# abpf.net
KiCad netlist of a schematic drawn in EAGLE
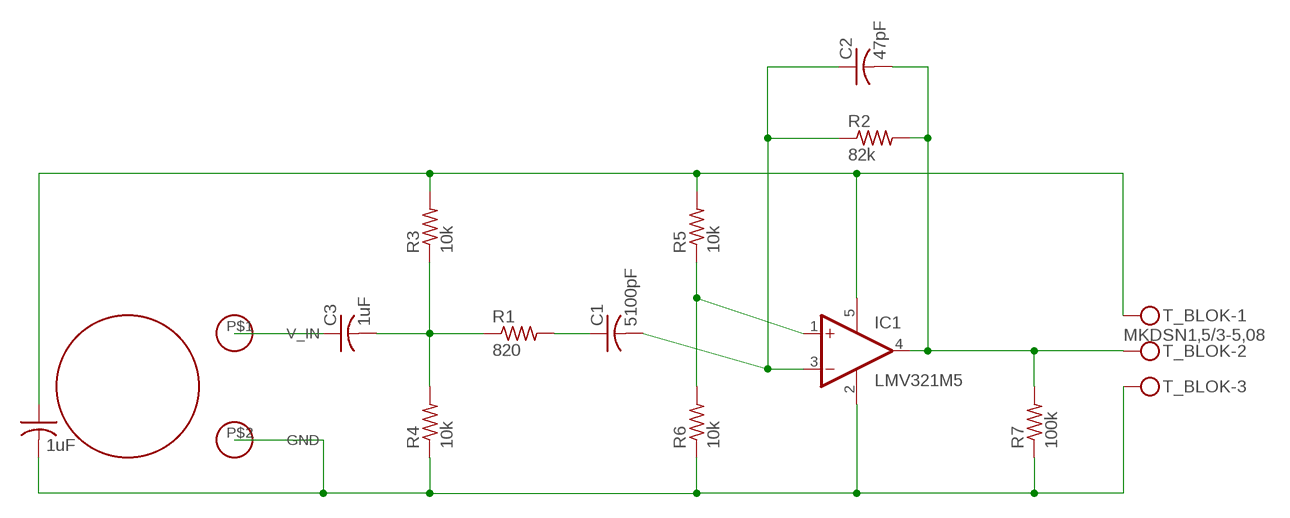
[diagram p0: schematic, sheet 1]

(export (version "E")
  (design (tool "Eeschema 10.0.6"))
  (components
    (comp (ref "C1")
      (value "5100pF")
      (footprint "eagle-import:C0805")
      (libsource (lib "eagle-import") (part "C-USC0805"))
    )
    (comp (ref "C2")
      (value "47pF")
      (footprint "eagle-import:C0805")
      (libsource (lib "eagle-import") (part "C-USC0805"))
    )
    (comp (ref "C3")
      (value "1uF")
      (footprint "eagle-import:C0805")
      (libsource (lib "eagle-import") (part "C-USC0805"))
    )
    (comp (ref "C4")
      (value "1uF")
      (footprint "eagle-import:C0805")
      (libsource (lib "eagle-import") (part "C-USC0805"))
    )
    (comp (ref "IC1")
      (value "LMV321M5")
      (footprint "eagle-import:SOT23-5")
      (libsource (lib "eagle-import") (part "LMV321?M5"))
    )
    (comp (ref "R1")
      (value "820")
      (footprint "eagle-import:R0805")
      (libsource (lib "eagle-import") (part "R-US_R0805"))
    )
    (comp (ref "R2")
      (value "82k")
      (footprint "eagle-import:R0805")
      (libsource (lib "eagle-import") (part "R-US_R0805"))
    )
    (comp (ref "R3")
      (value "10k")
      (footprint "eagle-import:R0805")
      (libsource (lib "eagle-import") (part "R-US_R0805"))
    )
    (comp (ref "R4")
      (value "10k")
      (footprint "eagle-import:R0805")
      (libsource (lib "eagle-import") (part "R-US_R0805"))
    )
    (comp (ref "R5")
      (value "10k")
      (footprint "eagle-import:R0805")
      (libsource (lib "eagle-import") (part "R-US_R0805"))
    )
    (comp (ref "R6")
      (value "10k")
      (footprint "eagle-import:R0805")
      (libsource (lib "eagle-import") (part "R-US_R0805"))
    )
    (comp (ref "R7")
      (value "100k")
      (footprint "eagle-import:R0805")
      (libsource (lib "eagle-import") (part "R-US_R0805"))
    )
    (comp (ref "T_BLOK")
      (value "MKDSN1,5/3-5,08")
      (footprint "eagle-import:MKDSN1,5_3-5,08")
      (libsource (lib "eagle-import") (part "MKDSN1,5/3-5,08"))
    )
    (comp (ref "U$1")
      (value "10MM_USONIC")
      (footprint "eagle-import:10MM_USONIC")
      (libsource (lib "eagle-import") (part "10MM_USONIC"))
    )
  )
  (nets
    (net (code "1") (name "Net-(C1-Pad1)") (class "Default")
      (node (ref "C1") (pin "1") (pinfunction "1_1") (pintype "passive"))
      (node (ref "R1") (pin "2") (pinfunction "2_2") (pintype "passive"))
    )
    (net (code "2") (name "Net-(C3-Pad2)") (class "Default")
      (node (ref "C3") (pin "2") (pinfunction "2_2") (pintype "passive"))
      (node (ref "R1") (pin "1") (pinfunction "1_1") (pintype "passive"))
      (node (ref "R3") (pin "1") (pinfunction "1_1") (pintype "passive"))
      (node (ref "R4") (pin "2") (pinfunction "2_2") (pintype "passive"))
    )
    (net (code "3") (name "Net-(IC1-+IN)") (class "Default")
      (node (ref "IC1") (pin "1") (pinfunction "+IN_1") (pintype "input"))
      (node (ref "R5") (pin "1") (pinfunction "1_1") (pintype "passive"))
      (node (ref "R6") (pin "2") (pinfunction "2_2") (pintype "passive"))
    )
    (net (code "4") (name "Net-(IC1--IN)") (class "Default")
      (node (ref "C1") (pin "2") (pinfunction "2_2") (pintype "passive"))
      (node (ref "C2") (pin "1") (pinfunction "1_1") (pintype "passive"))
      (node (ref "IC1") (pin "3") (pinfunction "-IN_3") (pintype "input"))
      (node (ref "R2") (pin "1") (pinfunction "1_1") (pintype "passive"))
    )
    (net (code "5") (name "Net-(IC1-OUT)") (class "Default")
      (node (ref "C2") (pin "2") (pinfunction "2_2") (pintype "passive"))
      (node (ref "IC1") (pin "4") (pinfunction "OUT_4") (pintype "output"))
      (node (ref "R2") (pin "2") (pinfunction "2_2") (pintype "passive"))
      (node (ref "R7") (pin "2") (pinfunction "2_2") (pintype "passive"))
      (node (ref "T_BLOK") (pin "2") (pinfunction "KL_2") (pintype "passive"))
    )
    (net (code "6") (name "Net-(IC1-V+)") (class "Default")
      (node (ref "C4") (pin "1") (pinfunction "1_1") (pintype "passive"))
      (node (ref "IC1") (pin "5") (pinfunction "V+_5") (pintype "power_in"))
      (node (ref "R3") (pin "2") (pinfunction "2_2") (pintype "passive"))
      (node (ref "R5") (pin "2") (pinfunction "2_2") (pintype "passive"))
      (node (ref "T_BLOK") (pin "1") (pinfunction "KL_1") (pintype "passive"))
    )
    (net (code "7") (name "Net-(IC1-V-)") (class "Default")
      (node (ref "C4") (pin "2") (pinfunction "2_2") (pintype "passive"))
      (node (ref "IC1") (pin "2") (pinfunction "V-_2") (pintype "power_in"))
      (node (ref "R4") (pin "1") (pinfunction "1_1") (pintype "passive"))
      (node (ref "R6") (pin "1") (pinfunction "1_1") (pintype "passive"))
      (node (ref "R7") (pin "1") (pinfunction "1_1") (pintype "passive"))
      (node (ref "T_BLOK") (pin "3") (pinfunction "KL_3") (pintype "passive"))
      (node (ref "U$1") (pin "P$2") (pinfunction "GND_P$2") (pintype "bidirectional"))
    )
    (net (code "8") (name "Net-(U$1-V_IN)") (class "Default")
      (node (ref "C3") (pin "1") (pinfunction "1_1") (pintype "passive"))
      (node (ref "U$1") (pin "P$1") (pinfunction "V_IN_P$1") (pintype "bidirectional"))
    )
  )
)
